# tinyI2C.net
KiCad netlist of a schematic drawn in EAGLE
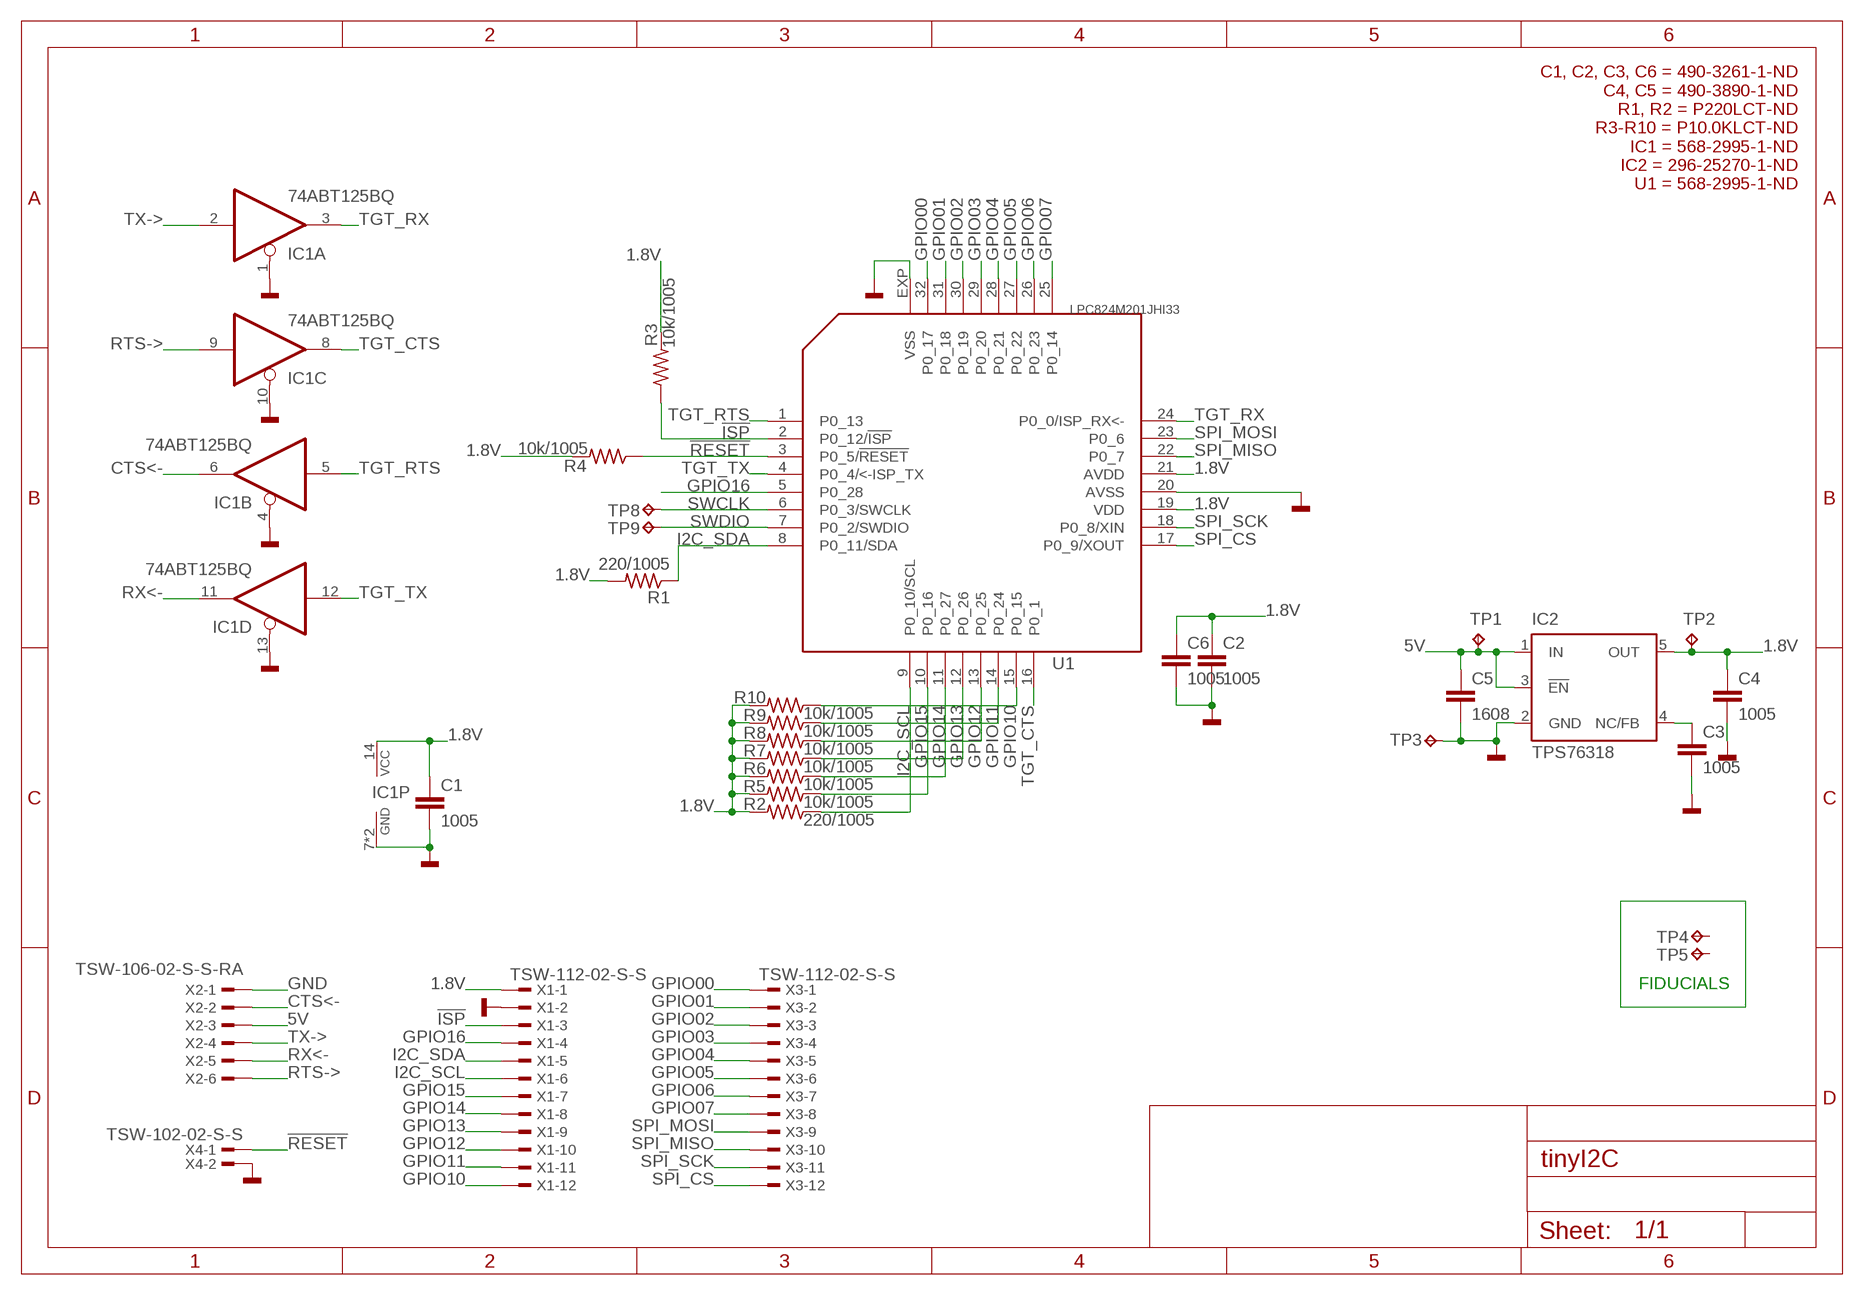
[diagram p0: schematic, sheet 1]

(export (version "E")
  (design (tool "Eeschema 10.0.6"))
  (components
    (comp (ref "C1")
      (value "1005")
      (footprint "eagle-import:C1005")
      (libsource (lib "eagle-import") (part "C-EUC1005"))
    )
    (comp (ref "C2")
      (value "1005")
      (footprint "eagle-import:C1005")
      (libsource (lib "eagle-import") (part "C-EUC1005"))
    )
    (comp (ref "C3")
      (value "1005")
      (footprint "eagle-import:C1005")
      (libsource (lib "eagle-import") (part "C-EUC1005"))
    )
    (comp (ref "C4")
      (value "1005")
      (footprint "eagle-import:C1005")
      (libsource (lib "eagle-import") (part "C-EUC1005"))
    )
    (comp (ref "C5")
      (value "1608")
      (footprint "eagle-import:C1608")
      (libsource (lib "eagle-import") (part "C-EUC1608"))
    )
    (comp (ref "C6")
      (value "1005")
      (footprint "eagle-import:C1005")
      (libsource (lib "eagle-import") (part "C-EUC1005"))
    )
    (comp (ref "IC1")
      (value "74ABT125BQ")
      (footprint "eagle-import:DHVQFN14")
      (libsource (lib "eagle-import") (part "74125BQABT"))
    )
    (comp (ref "IC2")
      (value "TPS76318")
      (footprint "eagle-import:SOT23-DBV")
      (fields (field (name "MF") "TEXAS INSTRUMENT CONNECTORS") (field (name "MPN") "TPS77018DBVR"))
      (libsource (lib "eagle-import") (part "TPS77018"))
    )
    (comp (ref "R1")
      (value "220/1005")
      (footprint "eagle-import:R1005")
      (libsource (lib "eagle-import") (part "R-US_R1005"))
    )
    (comp (ref "R2")
      (value "220/1005")
      (footprint "eagle-import:R1005")
      (libsource (lib "eagle-import") (part "R-US_R1005"))
    )
    (comp (ref "R3")
      (value "10k/1005")
      (footprint "eagle-import:R1005")
      (libsource (lib "eagle-import") (part "R-US_R1005"))
    )
    (comp (ref "R4")
      (value "10k/1005")
      (footprint "eagle-import:R1005")
      (libsource (lib "eagle-import") (part "R-US_R1005"))
    )
    (comp (ref "R5")
      (value "10k/1005")
      (footprint "eagle-import:R1005")
      (libsource (lib "eagle-import") (part "R-US_R1005"))
    )
    (comp (ref "R6")
      (value "10k/1005")
      (footprint "eagle-import:R1005")
      (libsource (lib "eagle-import") (part "R-US_R1005"))
    )
    (comp (ref "R7")
      (value "10k/1005")
      (footprint "eagle-import:R1005")
      (libsource (lib "eagle-import") (part "R-US_R1005"))
    )
    (comp (ref "R8")
      (value "10k/1005")
      (footprint "eagle-import:R1005")
      (libsource (lib "eagle-import") (part "R-US_R1005"))
    )
    (comp (ref "R9")
      (value "10k/1005")
      (footprint "eagle-import:R1005")
      (libsource (lib "eagle-import") (part "R-US_R1005"))
    )
    (comp (ref "R10")
      (value "10k/1005")
      (footprint "eagle-import:R1005")
      (libsource (lib "eagle-import") (part "R-US_R1005"))
    )
    (comp (ref "TP1")
      (value "TPTP07R")
      (footprint "eagle-import:TP07R")
      (libsource (lib "eagle-import") (part "TPTP07R"))
    )
    (comp (ref "TP2")
      (value "TPTP07R")
      (footprint "eagle-import:TP07R")
      (libsource (lib "eagle-import") (part "TPTP07R"))
    )
    (comp (ref "TP3")
      (value "TPTP07R")
      (footprint "eagle-import:TP07R")
      (libsource (lib "eagle-import") (part "TPTP07R"))
    )
    (comp (ref "TP4")
      (value "TPTP10R")
      (footprint "eagle-import:TP10R")
      (libsource (lib "eagle-import") (part "TPTP10R"))
    )
    (comp (ref "TP5")
      (value "TPTP10R")
      (footprint "eagle-import:TP10R")
      (libsource (lib "eagle-import") (part "TPTP10R"))
    )
    (comp (ref "TP8")
      (value "TPTP07R")
      (footprint "eagle-import:TP07R")
      (libsource (lib "eagle-import") (part "TPTP07R"))
    )
    (comp (ref "TP9")
      (value "TPTP07R")
      (footprint "eagle-import:TP07R")
      (libsource (lib "eagle-import") (part "TPTP07R"))
    )
    (comp (ref "U1")
      (value "LPC824M201JHI33")
      (footprint "eagle-import:HVQFN33")
      (libsource (lib "eagle-import") (part "LPC824M201JHI33"))
    )
    (comp (ref "X1")
      (value "TSW-112-02-S-S")
      (footprint "eagle-import:TSW-112-02-S-S")
      (libsource (lib "eagle-import") (part "TSW-112-02-S-S"))
    )
    (comp (ref "X2")
      (value "TSW-106-02-S-S-RA")
      (footprint "eagle-import:TSW-106-02-S-S-RA")
      (libsource (lib "eagle-import") (part "TSW-106-02-S-S-RA"))
    )
    (comp (ref "X3")
      (value "TSW-112-02-S-S")
      (footprint "eagle-import:TSW-112-02-S-S")
      (libsource (lib "eagle-import") (part "TSW-112-02-S-S"))
    )
    (comp (ref "X4")
      (value "TSW-102-02-S-S")
      (footprint "eagle-import:TSW-102-02-S-S")
      (libsource (lib "eagle-import") (part "TSW-102-02-S-S"))
    )
  )
  (nets
    (net (code "1") (name "/1.8V") (class "Default")
      (node (ref "C1") (pin "1") (pinfunction "1_1") (pintype "passive"))
      (node (ref "C2") (pin "1") (pinfunction "1_1") (pintype "passive"))
      (node (ref "C4") (pin "1") (pinfunction "1_1") (pintype "passive"))
      (node (ref "C6") (pin "1") (pinfunction "1_1") (pintype "passive"))
      (node (ref "IC1") (pin "14") (pinfunction "VCC_14") (pintype "power_in"))
      (node (ref "IC2") (pin "5") (pinfunction "OUT_5") (pintype "passive"))
      (node (ref "R1") (pin "2") (pinfunction "2_2") (pintype "passive"))
      (node (ref "R10") (pin "2") (pinfunction "2_2") (pintype "passive"))
      (node (ref "R2") (pin "2") (pinfunction "2_2") (pintype "passive"))
      (node (ref "R3") (pin "2") (pinfunction "2_2") (pintype "passive"))
      (node (ref "R4") (pin "2") (pinfunction "2_2") (pintype "passive"))
      (node (ref "R5") (pin "2") (pinfunction "2_2") (pintype "passive"))
      (node (ref "R6") (pin "2") (pinfunction "2_2") (pintype "passive"))
      (node (ref "R7") (pin "2") (pinfunction "2_2") (pintype "passive"))
      (node (ref "R8") (pin "2") (pinfunction "2_2") (pintype "passive"))
      (node (ref "R9") (pin "2") (pinfunction "2_2") (pintype "passive"))
      (node (ref "TP2") (pin "TP") (pinfunction "TP_TP") (pintype "input"))
      (node (ref "U1") (pin "19") (pinfunction "VDD_19") (pintype "bidirectional"))
      (node (ref "U1") (pin "21") (pinfunction "AVDD_21") (pintype "bidirectional"))
      (node (ref "X1") (pin "1") (pinfunction "1_1") (pintype "passive"))
    )
    (net (code "2") (name "/5V") (class "Default")
      (node (ref "C5") (pin "1") (pinfunction "1_1") (pintype "passive"))
      (node (ref "IC2") (pin "1") (pinfunction "IN_1") (pintype "input"))
      (node (ref "IC2") (pin "3") (pinfunction "~{EN}_3") (pintype "input"))
      (node (ref "TP1") (pin "TP") (pinfunction "TP_TP") (pintype "input"))
      (node (ref "X2") (pin "3") (pinfunction "1_3") (pintype "passive"))
    )
    (net (code "3") (name "/CTS<-") (class "Default")
      (node (ref "IC1") (pin "6") (pinfunction "O_6") (pintype "tri_state"))
      (node (ref "X2") (pin "2") (pinfunction "1_2") (pintype "passive"))
    )
    (net (code "4") (name "/GPIO00") (class "Default")
      (node (ref "U1") (pin "32") (pinfunction "P0_17_32") (pintype "bidirectional"))
      (node (ref "X3") (pin "1") (pinfunction "1_1") (pintype "passive"))
    )
    (net (code "5") (name "/GPIO01") (class "Default")
      (node (ref "U1") (pin "31") (pinfunction "P0_18_31") (pintype "bidirectional"))
      (node (ref "X3") (pin "2") (pinfunction "1_2") (pintype "passive"))
    )
    (net (code "6") (name "/GPIO02") (class "Default")
      (node (ref "U1") (pin "30") (pinfunction "P0_19_30") (pintype "bidirectional"))
      (node (ref "X3") (pin "3") (pinfunction "1_3") (pintype "passive"))
    )
    (net (code "7") (name "/GPIO03") (class "Default")
      (node (ref "U1") (pin "29") (pinfunction "P0_20_29") (pintype "bidirectional"))
      (node (ref "X3") (pin "4") (pinfunction "1_4") (pintype "passive"))
    )
    (net (code "8") (name "/GPIO04") (class "Default")
      (node (ref "U1") (pin "28") (pinfunction "P0_21_28") (pintype "bidirectional"))
      (node (ref "X3") (pin "5") (pinfunction "1_5") (pintype "passive"))
    )
    (net (code "9") (name "/GPIO05") (class "Default")
      (node (ref "U1") (pin "27") (pinfunction "P0_22_27") (pintype "bidirectional"))
      (node (ref "X3") (pin "6") (pinfunction "1_6") (pintype "passive"))
    )
    (net (code "10") (name "/GPIO06") (class "Default")
      (node (ref "U1") (pin "26") (pinfunction "P0_23_26") (pintype "bidirectional"))
      (node (ref "X3") (pin "7") (pinfunction "1_7") (pintype "passive"))
    )
    (net (code "11") (name "/GPIO07") (class "Default")
      (node (ref "U1") (pin "25") (pinfunction "P0_14_25") (pintype "bidirectional"))
      (node (ref "X3") (pin "8") (pinfunction "1_8") (pintype "passive"))
    )
    (net (code "12") (name "/GPIO10") (class "Default")
      (node (ref "R10") (pin "1") (pinfunction "1_1") (pintype "passive"))
      (node (ref "U1") (pin "15") (pinfunction "P0_15_15") (pintype "bidirectional"))
      (node (ref "X1") (pin "12") (pinfunction "1_12") (pintype "passive"))
    )
    (net (code "13") (name "/GPIO11") (class "Default")
      (node (ref "R9") (pin "1") (pinfunction "1_1") (pintype "passive"))
      (node (ref "U1") (pin "14") (pinfunction "P0_24_14") (pintype "bidirectional"))
      (node (ref "X1") (pin "11") (pinfunction "1_11") (pintype "passive"))
    )
    (net (code "14") (name "/GPIO12") (class "Default")
      (node (ref "R8") (pin "1") (pinfunction "1_1") (pintype "passive"))
      (node (ref "U1") (pin "13") (pinfunction "P0_25_13") (pintype "bidirectional"))
      (node (ref "X1") (pin "10") (pinfunction "1_10") (pintype "passive"))
    )
    (net (code "15") (name "/GPIO13") (class "Default")
      (node (ref "R7") (pin "1") (pinfunction "1_1") (pintype "passive"))
      (node (ref "U1") (pin "12") (pinfunction "P0_26_12") (pintype "bidirectional"))
      (node (ref "X1") (pin "9") (pinfunction "1_9") (pintype "passive"))
    )
    (net (code "16") (name "/GPIO14") (class "Default")
      (node (ref "R6") (pin "1") (pinfunction "1_1") (pintype "passive"))
      (node (ref "U1") (pin "11") (pinfunction "P0_27_11") (pintype "bidirectional"))
      (node (ref "X1") (pin "8") (pinfunction "1_8") (pintype "passive"))
    )
    (net (code "17") (name "/GPIO15") (class "Default")
      (node (ref "R5") (pin "1") (pinfunction "1_1") (pintype "passive"))
      (node (ref "U1") (pin "10") (pinfunction "P0_16_10") (pintype "bidirectional"))
      (node (ref "X1") (pin "7") (pinfunction "1_7") (pintype "passive"))
    )
    (net (code "18") (name "/GPIO16") (class "Default")
      (node (ref "U1") (pin "5") (pinfunction "P0_28_5") (pintype "bidirectional"))
      (node (ref "X1") (pin "4") (pinfunction "1_4") (pintype "passive"))
    )
    (net (code "19") (name "/I2C_SCL") (class "Default")
      (node (ref "R2") (pin "1") (pinfunction "1_1") (pintype "passive"))
      (node (ref "U1") (pin "9") (pinfunction "P0_10/SCL_9") (pintype "bidirectional"))
      (node (ref "X1") (pin "6") (pinfunction "1_6") (pintype "passive"))
    )
    (net (code "20") (name "/I2C_SDA") (class "Default")
      (node (ref "R1") (pin "1") (pinfunction "1_1") (pintype "passive"))
      (node (ref "U1") (pin "8") (pinfunction "P0_11/SDA_8") (pintype "bidirectional"))
      (node (ref "X1") (pin "5") (pinfunction "1_5") (pintype "passive"))
    )
    (net (code "21") (name "/RTS->") (class "Default")
      (node (ref "IC1") (pin "9") (pinfunction "I_9") (pintype "input"))
      (node (ref "X2") (pin "6") (pinfunction "1_6") (pintype "passive"))
    )
    (net (code "22") (name "/RX<-") (class "Default")
      (node (ref "IC1") (pin "11") (pinfunction "O_11") (pintype "tri_state"))
      (node (ref "X2") (pin "5") (pinfunction "1_5") (pintype "passive"))
    )
    (net (code "23") (name "/SPI_CS") (class "Default")
      (node (ref "U1") (pin "17") (pinfunction "P0_9/XOUT_17") (pintype "bidirectional"))
      (node (ref "X3") (pin "12") (pinfunction "1_12") (pintype "passive"))
    )
    (net (code "24") (name "/SPI_MISO") (class "Default")
      (node (ref "U1") (pin "22") (pinfunction "P0_7_22") (pintype "bidirectional"))
      (node (ref "X3") (pin "10") (pinfunction "1_10") (pintype "passive"))
    )
    (net (code "25") (name "/SPI_MOSI") (class "Default")
      (node (ref "U1") (pin "23") (pinfunction "P0_6_23") (pintype "bidirectional"))
      (node (ref "X3") (pin "9") (pinfunction "1_9") (pintype "passive"))
    )
    (net (code "26") (name "/SPI_SCK") (class "Default")
      (node (ref "U1") (pin "18") (pinfunction "P0_8/XIN_18") (pintype "bidirectional"))
      (node (ref "X3") (pin "11") (pinfunction "1_11") (pintype "passive"))
    )
    (net (code "27") (name "/SWCLK") (class "Default")
      (node (ref "TP8") (pin "TP") (pinfunction "TP_TP") (pintype "input"))
      (node (ref "U1") (pin "6") (pinfunction "P0_3/SWCLK_6") (pintype "bidirectional"))
    )
    (net (code "28") (name "/SWDIO") (class "Default")
      (node (ref "TP9") (pin "TP") (pinfunction "TP_TP") (pintype "input"))
      (node (ref "U1") (pin "7") (pinfunction "P0_2/SWDIO_7") (pintype "bidirectional"))
    )
    (net (code "29") (name "/TGT_CTS") (class "Default")
      (node (ref "IC1") (pin "8") (pinfunction "O_8") (pintype "tri_state"))
      (node (ref "U1") (pin "16") (pinfunction "P0_1_16") (pintype "bidirectional"))
    )
    (net (code "30") (name "/TGT_RTS") (class "Default")
      (node (ref "IC1") (pin "5") (pinfunction "I_5") (pintype "input"))
      (node (ref "U1") (pin "1") (pinfunction "P0_13_1") (pintype "bidirectional"))
    )
    (net (code "31") (name "/TGT_RX") (class "Default")
      (node (ref "IC1") (pin "3") (pinfunction "O_3") (pintype "tri_state"))
      (node (ref "U1") (pin "24") (pinfunction "P0_0/ISP_RX<-_24") (pintype "bidirectional"))
    )
    (net (code "32") (name "/TGT_TX") (class "Default")
      (node (ref "IC1") (pin "12") (pinfunction "I_12") (pintype "input"))
      (node (ref "U1") (pin "4") (pinfunction "P0_4/<-ISP_TX_4") (pintype "bidirectional"))
    )
    (net (code "33") (name "/TX->") (class "Default")
      (node (ref "IC1") (pin "2") (pinfunction "I_2") (pintype "input"))
      (node (ref "X2") (pin "4") (pinfunction "1_4") (pintype "passive"))
    )
    (net (code "34") (name "/~{ISP}") (class "Default")
      (node (ref "R3") (pin "1") (pinfunction "1_1") (pintype "passive"))
      (node (ref "U1") (pin "2") (pinfunction "P0_12/~{ISP}_2") (pintype "bidirectional"))
      (node (ref "X1") (pin "3") (pinfunction "1_3") (pintype "passive"))
    )
    (net (code "35") (name "/~{RESET}") (class "Default")
      (node (ref "R4") (pin "1") (pinfunction "1_1") (pintype "passive"))
      (node (ref "U1") (pin "3") (pinfunction "P0_5/~{RESET}_3") (pintype "bidirectional"))
      (node (ref "X4") (pin "1") (pinfunction "1_1") (pintype "passive"))
    )
    (net (code "36") (name "GND") (class "Default")
      (node (ref "C1") (pin "2") (pinfunction "2_2") (pintype "passive"))
      (node (ref "C2") (pin "2") (pinfunction "2_2") (pintype "passive"))
      (node (ref "C3") (pin "2") (pinfunction "2_2") (pintype "passive"))
      (node (ref "C4") (pin "2") (pinfunction "2_2") (pintype "passive"))
      (node (ref "C5") (pin "2") (pinfunction "2_2") (pintype "passive"))
      (node (ref "C6") (pin "2") (pinfunction "2_2") (pintype "passive"))
      (node (ref "IC1") (pin "1") (pinfunction "OE_1") (pintype "input"))
      (node (ref "IC1") (pin "10") (pinfunction "OE_10") (pintype "input"))
      (node (ref "IC1") (pin "13") (pinfunction "OE_13") (pintype "input"))
      (node (ref "IC1") (pin "4") (pinfunction "OE_4") (pintype "input"))
      (node (ref "IC1") (pin "7") (pinfunction "GND_7") (pintype "power_in"))
      (node (ref "IC1") (pin "EXP") (pinfunction "GND_EXP") (pintype "power_in"))
      (node (ref "IC2") (pin "2") (pinfunction "GND_2") (pintype "power_in"))
      (node (ref "TP3") (pin "TP") (pinfunction "TP_TP") (pintype "input"))
      (node (ref "U1") (pin "20") (pinfunction "AVSS_20") (pintype "bidirectional"))
      (node (ref "U1") (pin "EXP") (pinfunction "VSS_EXP") (pintype "bidirectional"))
      (node (ref "X1") (pin "2") (pinfunction "1_2") (pintype "passive"))
      (node (ref "X2") (pin "1") (pinfunction "1_1") (pintype "passive"))
      (node (ref "X4") (pin "2") (pinfunction "1_2") (pintype "passive"))
    )
    (net (code "37") (name "Net-(IC2-NC{slash}FB)") (class "Default")
      (node (ref "C3") (pin "1") (pinfunction "1_1") (pintype "passive"))
      (node (ref "IC2") (pin "4") (pinfunction "NC/FB_4") (pintype "passive"))
    )
    (net (code "38") (name "unconnected-(TP4-PadTP)") (class "Default")
      (node (ref "TP4") (pin "TP") (pinfunction "TP_TP") (pintype "input"))
    )
    (net (code "39") (name "unconnected-(TP5-PadTP)") (class "Default")
      (node (ref "TP5") (pin "TP") (pinfunction "TP_TP") (pintype "input"))
    )
  )
)
